# vfd_controller.net
KiCad netlist of a schematic drawn in EAGLE
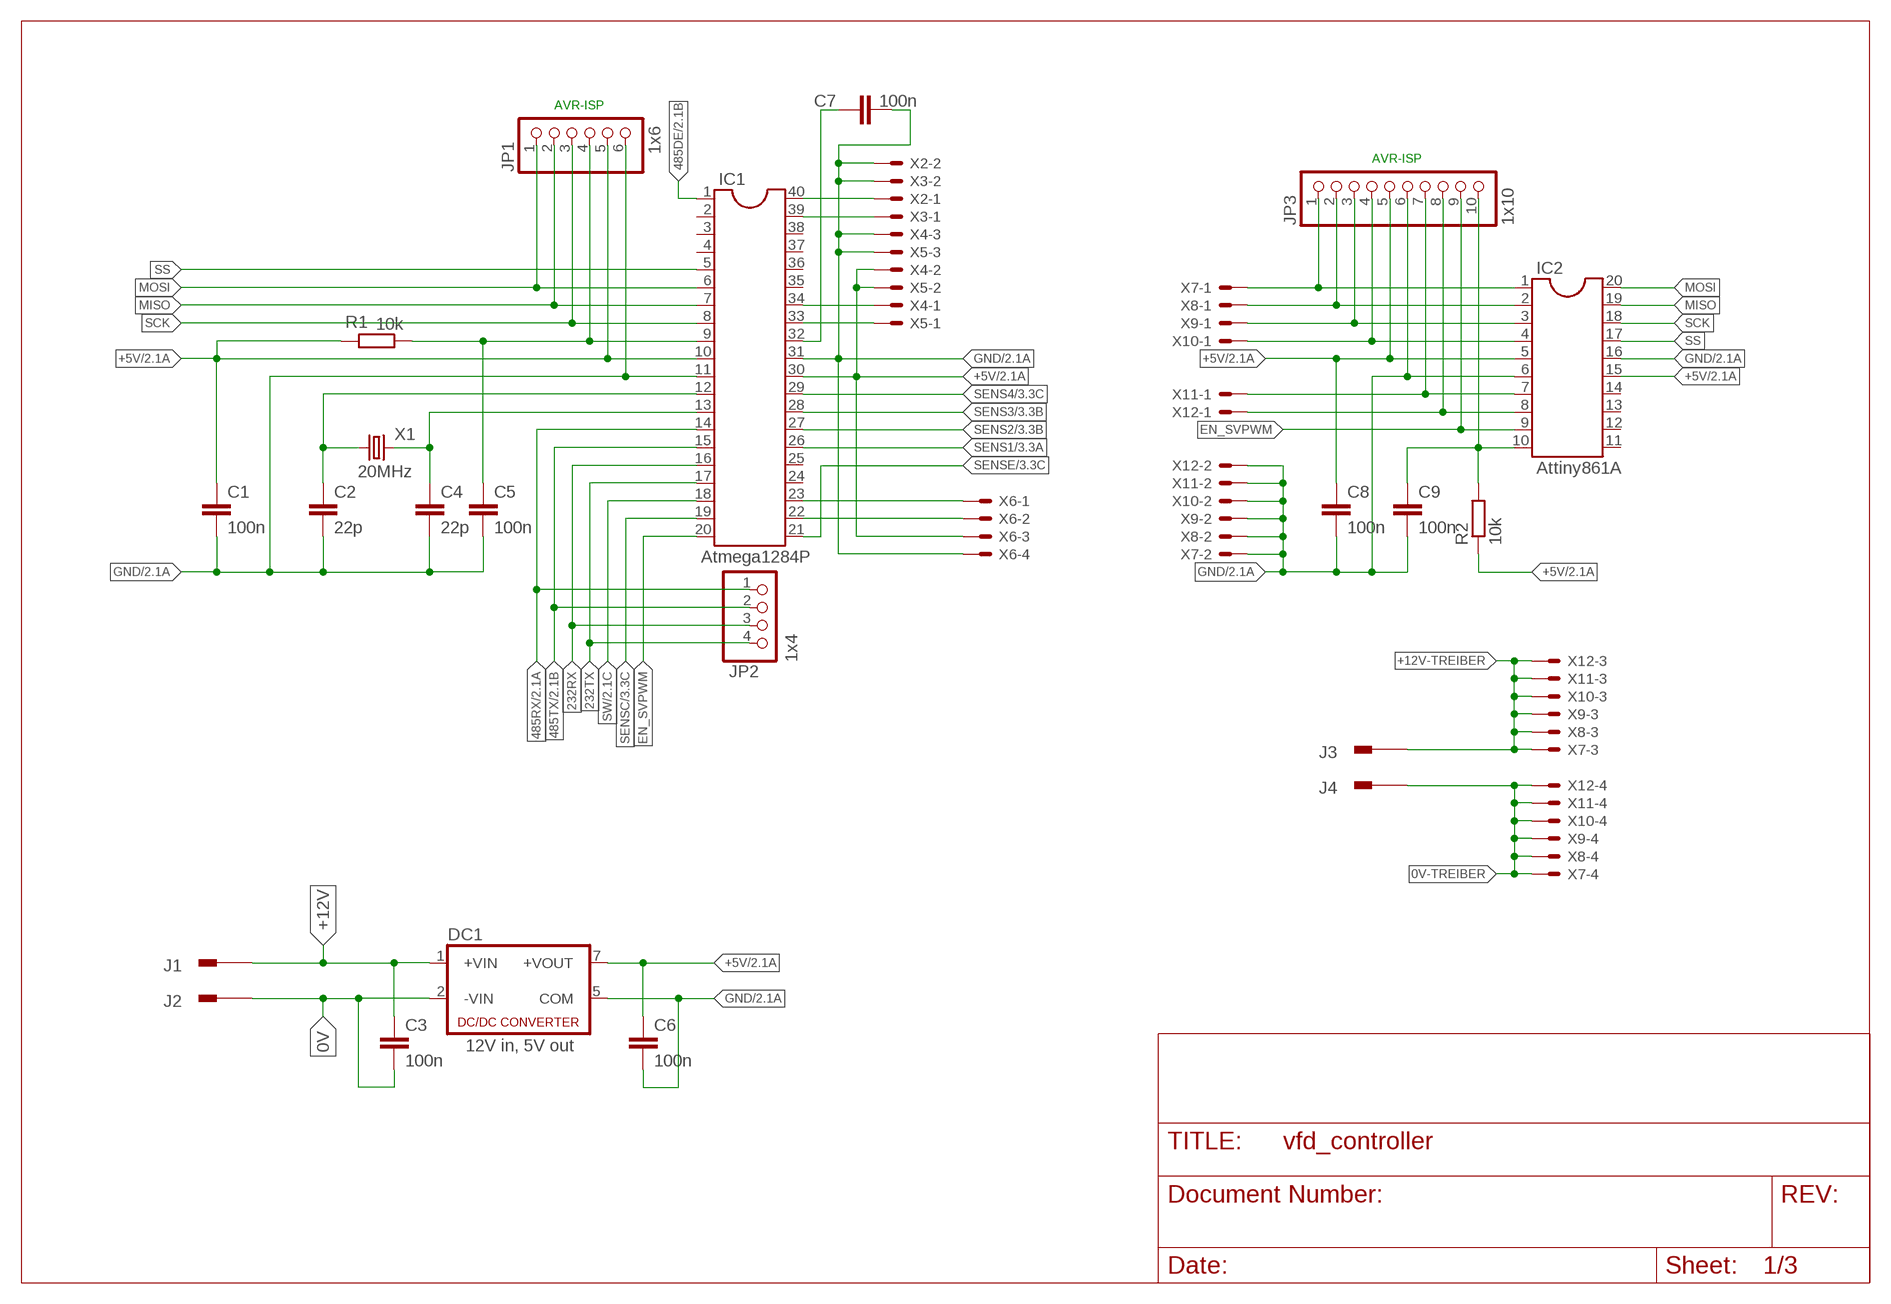
[diagram p0: schematic, sheet 1]
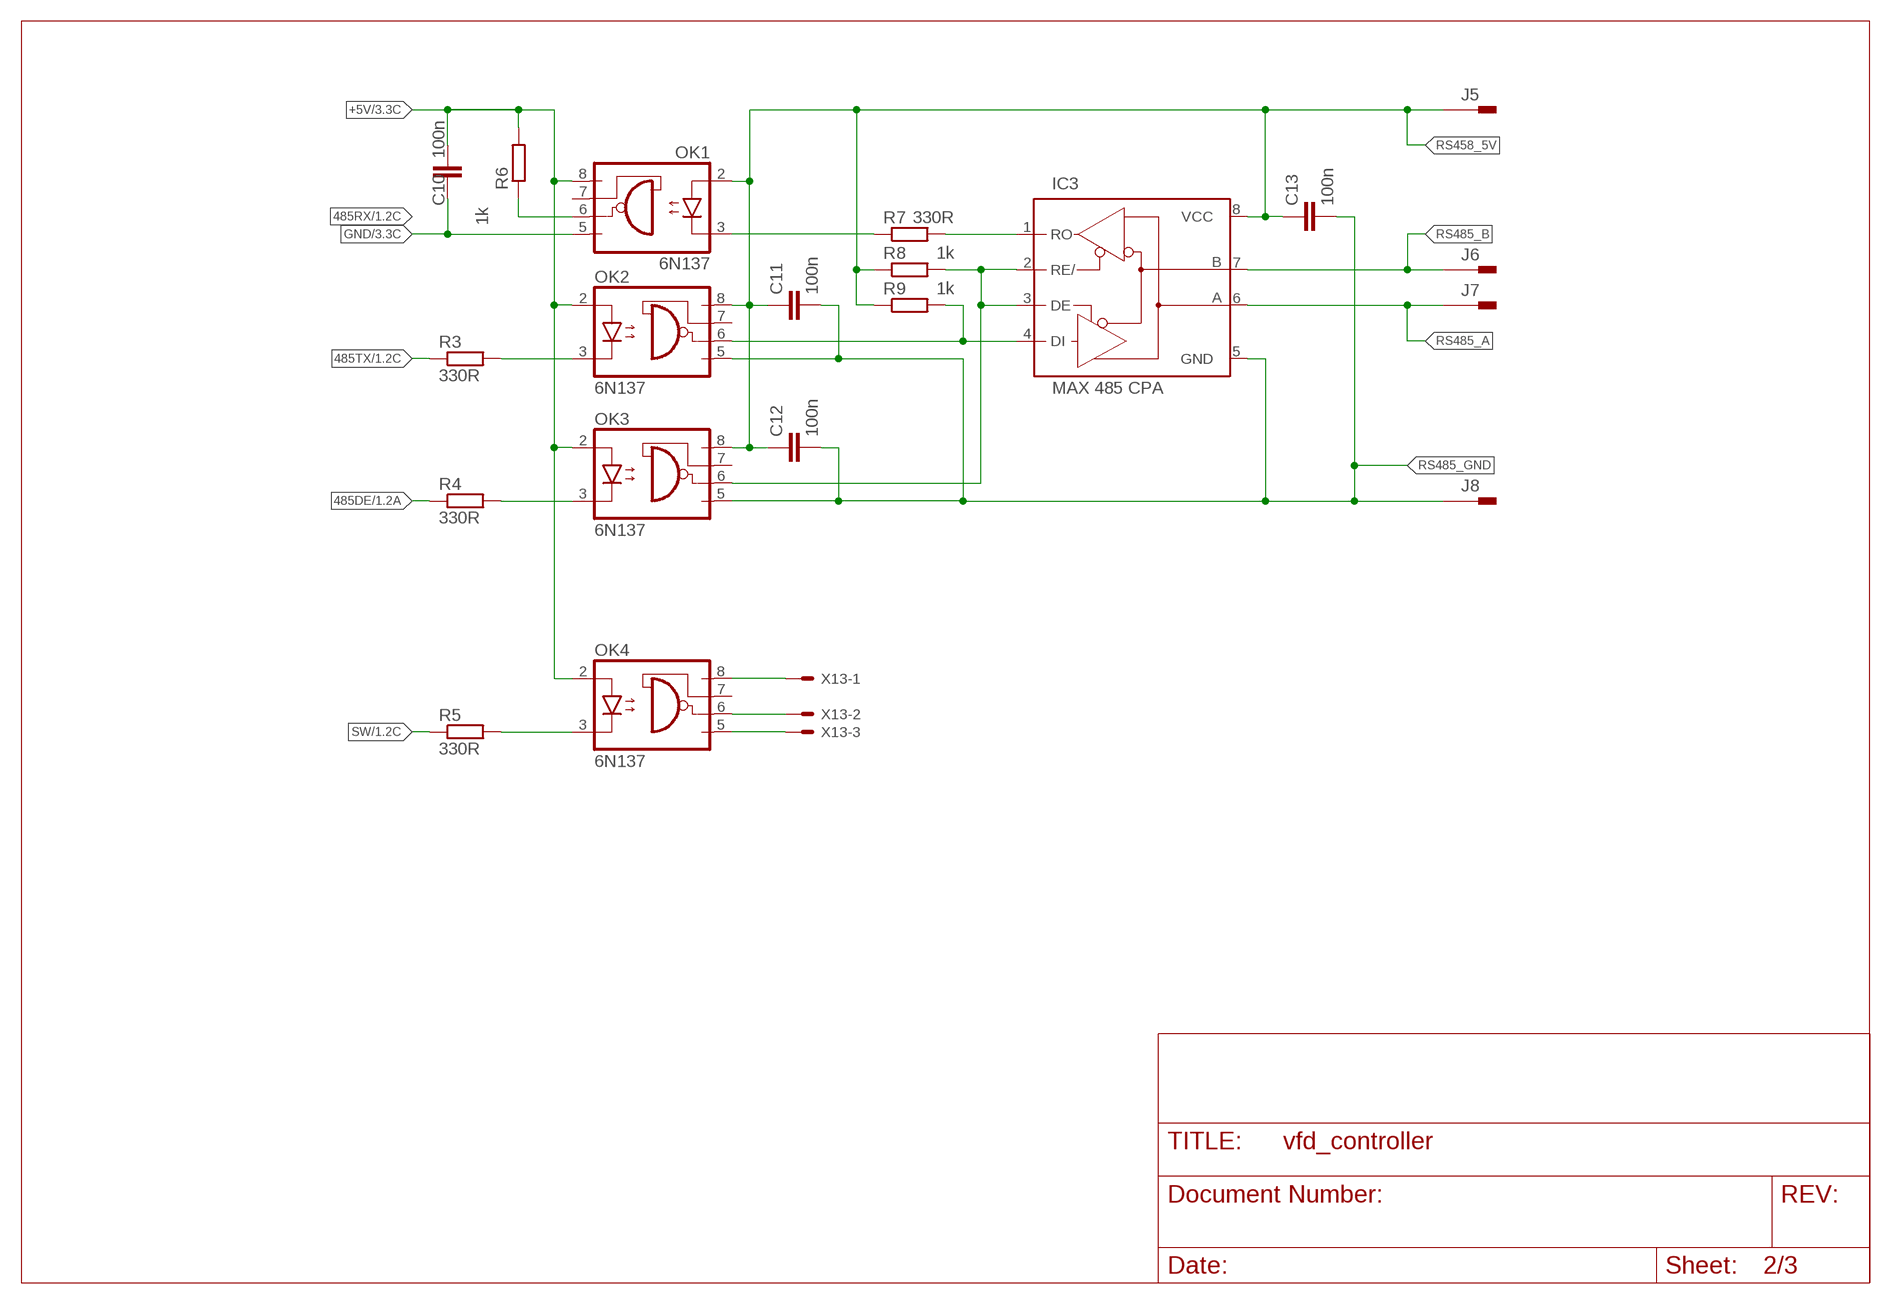
[diagram p1: schematic, sheet 2]
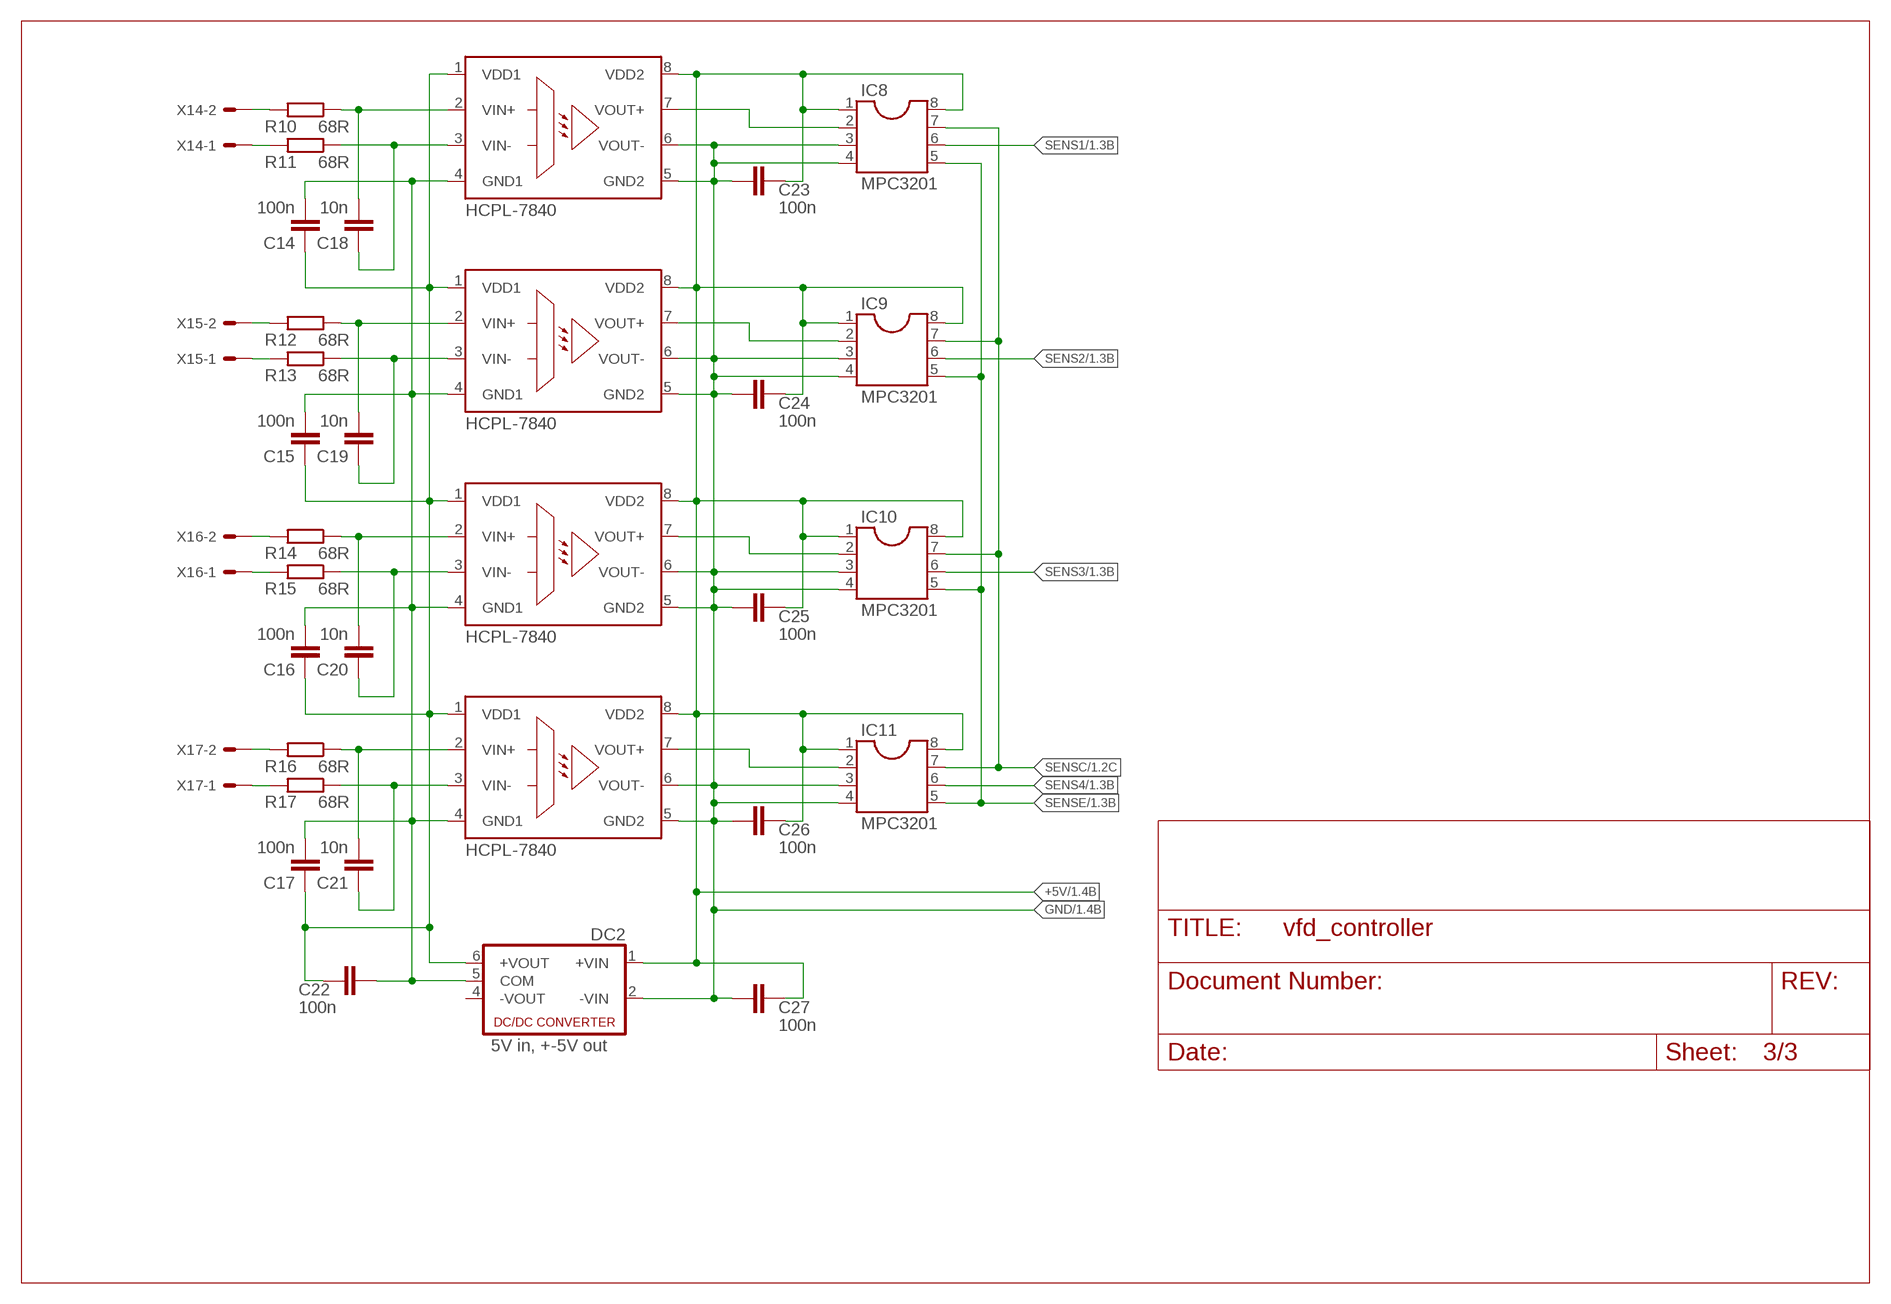
[diagram p2: schematic, sheet 3]

(export (version "E")
  (design (tool "Eeschema 10.0.6"))
  (components
    (comp (ref "C1")
      (value "100n")
      (footprint "eagle-import:C025-024X044")
      (libsource (lib "eagle-import") (part "C-EU025-024X044"))
    )
    (comp (ref "C2")
      (value "22p")
      (footprint "eagle-import:C025-024X044")
      (libsource (lib "eagle-import") (part "C-EU025-024X044"))
    )
    (comp (ref "C3")
      (value "100n")
      (footprint "eagle-import:C025-024X044")
      (libsource (lib "eagle-import") (part "C-EU025-024X044"))
    )
    (comp (ref "C4")
      (value "22p")
      (footprint "eagle-import:C025-024X044")
      (libsource (lib "eagle-import") (part "C-EU025-024X044"))
    )
    (comp (ref "C5")
      (value "100n")
      (footprint "eagle-import:C050-025X075")
      (libsource (lib "eagle-import") (part "C-EU050-025X075"))
    )
    (comp (ref "C6")
      (value "100n")
      (footprint "eagle-import:C050-025X075")
      (libsource (lib "eagle-import") (part "C-EU050-025X075"))
    )
    (comp (ref "C7")
      (value "100n")
      (footprint "eagle-import:C025-024X044")
      (libsource (lib "eagle-import") (part "C-EU025-024X044"))
    )
    (comp (ref "C8")
      (value "100n")
      (footprint "eagle-import:C025-024X044")
      (libsource (lib "eagle-import") (part "C-EU025-024X044"))
    )
    (comp (ref "C9")
      (value "100n")
      (footprint "eagle-import:C025-024X044")
      (libsource (lib "eagle-import") (part "C-EU025-024X044"))
    )
    (comp (ref "DC1")
      (value "12V in, 5V out")
      (footprint "eagle-import:MEV")
      (libsource (lib "eagle-import") (part "MEV"))
    )
    (comp (ref "IC1")
      (value "Atmega1284P")
      (footprint "eagle-import:DIL40")
      (libsource (lib "eagle-import") (part "DIL40"))
    )
    (comp (ref "IC2")
      (value "Attiny861A")
      (footprint "eagle-import:DIL20")
      (libsource (lib "eagle-import") (part "DIL20"))
    )
    (comp (ref "J1")
      (value "PIN2F061.200")
      (footprint "eagle-import:F061.200")
      (libsource (lib "eagle-import") (part "PIN2F061.200"))
    )
    (comp (ref "J2")
      (value "PIN2F061.200")
      (footprint "eagle-import:F061.200")
      (libsource (lib "eagle-import") (part "PIN2F061.200"))
    )
    (comp (ref "J3")
      (value "PIN2F061.200")
      (footprint "eagle-import:F061.200")
      (libsource (lib "eagle-import") (part "PIN2F061.200"))
    )
    (comp (ref "J4")
      (value "PIN2F061.200")
      (footprint "eagle-import:F061.200")
      (libsource (lib "eagle-import") (part "PIN2F061.200"))
    )
    (comp (ref "JP1")
      (value "1x6")
      (footprint "eagle-import:1X06")
      (libsource (lib "eagle-import") (part "PINHD-1X6"))
    )
    (comp (ref "JP2")
      (value "1x4")
      (footprint "eagle-import:1X04")
      (libsource (lib "eagle-import") (part "PINHD-1X4"))
    )
    (comp (ref "JP3")
      (value "1x10")
      (footprint "eagle-import:1X10")
      (libsource (lib "eagle-import") (part "PINHD-1X10"))
    )
    (comp (ref "R1")
      (value "10k")
      (footprint "eagle-import:0204V")
      (libsource (lib "eagle-import") (part "R-EU_0204/2V"))
    )
    (comp (ref "R2")
      (value "10k")
      (footprint "eagle-import:0207_12")
      (libsource (lib "eagle-import") (part "R-EU_0207/12"))
    )
    (comp (ref "X1")
      (value "20MHz")
      (footprint "eagle-import:HC49")
      (libsource (lib "eagle-import") (part "CRYSTALS-NOGND-HC49"))
    )
    (comp (ref "X2")
      (value "JST-XH-02-PIN-LONG-PAD")
      (footprint "eagle-import:JST-XH-02-PACKAGE-LONG-PAD")
      (fields (field (name "R") "JST XH2P ST"))
      (libsource (lib "eagle-import") (part "JST-XH-02-PIN-LONG-PAD"))
    )
    (comp (ref "X3")
      (value "JST-XH-02-PIN-LONG-PAD")
      (footprint "eagle-import:JST-XH-02-PACKAGE-LONG-PAD")
      (fields (field (name "R") "JST XH2P ST"))
      (libsource (lib "eagle-import") (part "JST-XH-02-PIN-LONG-PAD"))
    )
    (comp (ref "X4")
      (value "JST-XH-03-PIN-LONG-PAD")
      (footprint "eagle-import:JST-XH-03-PACKAGE-LONG-PAD")
      (fields (field (name "R") "JST XH3P ST"))
      (libsource (lib "eagle-import") (part "JST-XH-03-PIN-LONG-PAD"))
    )
    (comp (ref "X5")
      (value "JST-XH-03-PIN-LONG-PAD")
      (footprint "eagle-import:JST-XH-03-PACKAGE-LONG-PAD")
      (fields (field (name "R") "JST XH3P ST"))
      (libsource (lib "eagle-import") (part "JST-XH-03-PIN-LONG-PAD"))
    )
    (comp (ref "X6")
      (value "JST-XH-04-PIN-LONG-PAD")
      (footprint "eagle-import:JST-XH-04-PACKAGE-LONG-PAD")
      (fields (field (name "R") "JST XH4P ST"))
      (libsource (lib "eagle-import") (part "JST-XH-04-PIN-LONG-PAD"))
    )
    (comp (ref "X7")
      (value "JST-XH-04-PIN-LONG-PAD")
      (footprint "eagle-import:JST-XH-04-PACKAGE-LONG-PAD")
      (fields (field (name "R") "JST XH4P ST"))
      (libsource (lib "eagle-import") (part "JST-XH-04-PIN-LONG-PAD"))
    )
    (comp (ref "X8")
      (value "JST-XH-04-PIN-LONG-PAD")
      (footprint "eagle-import:JST-XH-04-PACKAGE-LONG-PAD")
      (fields (field (name "R") "JST XH4P ST"))
      (libsource (lib "eagle-import") (part "JST-XH-04-PIN-LONG-PAD"))
    )
    (comp (ref "X9")
      (value "JST-XH-04-PIN-LONG-PAD")
      (footprint "eagle-import:JST-XH-04-PACKAGE-LONG-PAD")
      (fields (field (name "R") "JST XH4P ST"))
      (libsource (lib "eagle-import") (part "JST-XH-04-PIN-LONG-PAD"))
    )
    (comp (ref "X10")
      (value "JST-XH-04-PIN-LONG-PAD")
      (footprint "eagle-import:JST-XH-04-PACKAGE-LONG-PAD")
      (fields (field (name "R") "JST XH4P ST"))
      (libsource (lib "eagle-import") (part "JST-XH-04-PIN-LONG-PAD"))
    )
    (comp (ref "X11")
      (value "JST-XH-04-PIN-LONG-PAD")
      (footprint "eagle-import:JST-XH-04-PACKAGE-LONG-PAD")
      (fields (field (name "R") "JST XH4P ST"))
      (libsource (lib "eagle-import") (part "JST-XH-04-PIN-LONG-PAD"))
    )
    (comp (ref "X12")
      (value "JST-XH-04-PIN-LONG-PAD")
      (footprint "eagle-import:JST-XH-04-PACKAGE-LONG-PAD")
      (fields (field (name "R") "JST XH4P ST"))
      (libsource (lib "eagle-import") (part "JST-XH-04-PIN-LONG-PAD"))
    )
    (comp (ref "C14")
      (value "100n")
      (footprint "eagle-import:C025-024X044")
      (libsource (lib "eagle-import") (part "C-EU025-024X044"))
    )
    (comp (ref "C15")
      (value "100n")
      (footprint "eagle-import:C050-025X075")
      (libsource (lib "eagle-import") (part "C-EU050-025X075"))
    )
    (comp (ref "C16")
      (value "100n")
      (footprint "eagle-import:C050-025X075")
      (libsource (lib "eagle-import") (part "C-EU050-025X075"))
    )
    (comp (ref "C17")
      (value "100n")
      (footprint "eagle-import:C050-025X075")
      (libsource (lib "eagle-import") (part "C-EU050-025X075"))
    )
    (comp (ref "C18")
      (value "10n")
      (footprint "eagle-import:C025-024X044")
      (libsource (lib "eagle-import") (part "C-EU025-024X044"))
    )
    (comp (ref "C19")
      (value "10n")
      (footprint "eagle-import:C025-024X044")
      (libsource (lib "eagle-import") (part "C-EU025-024X044"))
    )
    (comp (ref "C20")
      (value "10n")
      (footprint "eagle-import:C025-024X044")
      (libsource (lib "eagle-import") (part "C-EU025-024X044"))
    )
    (comp (ref "C21")
      (value "10n")
      (footprint "eagle-import:C025-024X044")
      (libsource (lib "eagle-import") (part "C-EU025-024X044"))
    )
    (comp (ref "C22")
      (value "100n")
      (footprint "eagle-import:C025-024X044")
      (libsource (lib "eagle-import") (part "C-EU025-024X044"))
    )
    (comp (ref "C23")
      (value "100n")
      (footprint "eagle-import:C025-024X044")
      (libsource (lib "eagle-import") (part "C-EU025-024X044"))
    )
    (comp (ref "C24")
      (value "100n")
      (footprint "eagle-import:C050-025X075")
      (libsource (lib "eagle-import") (part "C-EU050-025X075"))
    )
    (comp (ref "C25")
      (value "100n")
      (footprint "eagle-import:C050-025X075")
      (libsource (lib "eagle-import") (part "C-EU050-025X075"))
    )
    (comp (ref "C26")
      (value "100n")
      (footprint "eagle-import:C050-025X075")
      (libsource (lib "eagle-import") (part "C-EU050-025X075"))
    )
    (comp (ref "C27")
      (value "100n")
      (footprint "eagle-import:C025-024X044")
      (libsource (lib "eagle-import") (part "C-EU025-024X044"))
    )
    (comp (ref "DC2")
      (value "5V in, +-5V out")
      (footprint "eagle-import:NMA")
      (fields (field (name "MF") "C & D TECHNOLOGIES, INC") (field (name "MPN") "NMA0515SC"))
      (libsource (lib "eagle-import") (part "NMA"))
    )
    (comp (ref "IC4")
      (value "HCPL-7840")
      (footprint "eagle-import:DIL08")
      (fields (field (name "MPN") "HCPL-7800A#500"))
      (libsource (lib "eagle-import") (part "HCPL-7800"))
    )
    (comp (ref "IC5")
      (value "HCPL-7840")
      (footprint "eagle-import:DIL08")
      (fields (field (name "MPN") "HCPL-7800A#500"))
      (libsource (lib "eagle-import") (part "HCPL-7800"))
    )
    (comp (ref "IC6")
      (value "HCPL-7840")
      (footprint "eagle-import:DIL08")
      (fields (field (name "MPN") "HCPL-7800A#500"))
      (libsource (lib "eagle-import") (part "HCPL-7800"))
    )
    (comp (ref "IC7")
      (value "HCPL-7840")
      (footprint "eagle-import:DIL08")
      (fields (field (name "MPN") "HCPL-7800A#500"))
      (libsource (lib "eagle-import") (part "HCPL-7800"))
    )
    (comp (ref "IC8")
      (value "MPC3201")
      (footprint "eagle-import:DIL08")
      (libsource (lib "eagle-import") (part "DIL8"))
    )
    (comp (ref "IC9")
      (value "MPC3201")
      (footprint "eagle-import:DIL08")
      (libsource (lib "eagle-import") (part "DIL8"))
    )
    (comp (ref "IC10")
      (value "MPC3201")
      (footprint "eagle-import:DIL08")
      (libsource (lib "eagle-import") (part "DIL8"))
    )
    (comp (ref "IC11")
      (value "MPC3201")
      (footprint "eagle-import:DIL08")
      (libsource (lib "eagle-import") (part "DIL8"))
    )
    (comp (ref "R10")
      (value "68R")
      (footprint "eagle-import:0204_5")
      (libsource (lib "eagle-import") (part "resistor_348_R-EU_0204/5"))
    )
    (comp (ref "R11")
      (value "68R")
      (footprint "eagle-import:0204_5")
      (libsource (lib "eagle-import") (part "resistor_348_R-EU_0204/5"))
    )
    (comp (ref "R12")
      (value "68R")
      (footprint "eagle-import:0204_5")
      (libsource (lib "eagle-import") (part "resistor_348_R-EU_0204/5"))
    )
    (comp (ref "R13")
      (value "68R")
      (footprint "eagle-import:0204_5")
      (libsource (lib "eagle-import") (part "resistor_348_R-EU_0204/5"))
    )
    (comp (ref "R14")
      (value "68R")
      (footprint "eagle-import:0204_5")
      (libsource (lib "eagle-import") (part "resistor_348_R-EU_0204/5"))
    )
    (comp (ref "R15")
      (value "68R")
      (footprint "eagle-import:0204_5")
      (libsource (lib "eagle-import") (part "resistor_348_R-EU_0204/5"))
    )
    (comp (ref "R16")
      (value "68R")
      (footprint "eagle-import:0204_5")
      (libsource (lib "eagle-import") (part "resistor_348_R-EU_0204/5"))
    )
    (comp (ref "R17")
      (value "68R")
      (footprint "eagle-import:0204_5")
      (libsource (lib "eagle-import") (part "resistor_348_R-EU_0204/5"))
    )
    (comp (ref "X14")
      (value "JST-XH-02-PIN-LONG-PAD")
      (footprint "eagle-import:JST-XH-02-PACKAGE-LONG-PAD")
      (fields (field (name "R") "JST XH2P ST"))
      (libsource (lib "eagle-import") (part "JST-XH-02-PIN-LONG-PAD"))
    )
    (comp (ref "X15")
      (value "JST-XH-02-PIN-LONG-PAD")
      (footprint "eagle-import:JST-XH-02-PACKAGE-LONG-PAD")
      (fields (field (name "R") "JST XH2P ST"))
      (libsource (lib "eagle-import") (part "JST-XH-02-PIN-LONG-PAD"))
    )
    (comp (ref "X16")
      (value "JST-XH-02-PIN-LONG-PAD")
      (footprint "eagle-import:JST-XH-02-PACKAGE-LONG-PAD")
      (fields (field (name "R") "JST XH2P ST"))
      (libsource (lib "eagle-import") (part "JST-XH-02-PIN-LONG-PAD"))
    )
    (comp (ref "X17")
      (value "JST-XH-02-PIN-LONG-PAD")
      (footprint "eagle-import:JST-XH-02-PACKAGE-LONG-PAD")
      (fields (field (name "R") "JST XH2P ST"))
      (libsource (lib "eagle-import") (part "JST-XH-02-PIN-LONG-PAD"))
    )
    (comp (ref "C10")
      (value "100n")
      (footprint "eagle-import:C025-024X044")
      (libsource (lib "eagle-import") (part "resistor_348_C-EU025-024X044"))
    )
    (comp (ref "C11")
      (value "100n")
      (footprint "eagle-import:C025-024X044")
      (libsource (lib "eagle-import") (part "resistor_348_C-EU025-024X044"))
    )
    (comp (ref "C12")
      (value "100n")
      (footprint "eagle-import:C025-024X044")
      (libsource (lib "eagle-import") (part "resistor_348_C-EU025-024X044"))
    )
    (comp (ref "C13")
      (value "100n")
      (footprint "eagle-import:C025-024X044")
      (libsource (lib "eagle-import") (part "resistor_348_C-EU025-024X044"))
    )
    (comp (ref "IC3")
      (value "MAX 485 CPA")
      (footprint "eagle-import:DIL08")
      (libsource (lib "eagle-import") (part "MAX34PA68C"))
    )
    (comp (ref "J5")
      (value "PIN2F061.200")
      (footprint "eagle-import:F061.200")
      (libsource (lib "eagle-import") (part "PIN2F061.200"))
    )
    (comp (ref "J6")
      (value "PIN2F061.200")
      (footprint "eagle-import:F061.200")
      (libsource (lib "eagle-import") (part "PIN2F061.200"))
    )
    (comp (ref "J7")
      (value "PIN2F061.200")
      (footprint "eagle-import:F061.200")
      (libsource (lib "eagle-import") (part "PIN2F061.200"))
    )
    (comp (ref "J8")
      (value "PIN2F061.200")
      (footprint "eagle-import:F061.200")
      (libsource (lib "eagle-import") (part "PIN2F061.200"))
    )
    (comp (ref "OK1")
      (value "6N137")
      (footprint "eagle-import:DIL08")
      (libsource (lib "eagle-import") (part "6N137"))
    )
    (comp (ref "OK2")
      (value "6N137")
      (footprint "eagle-import:DIL08")
      (libsource (lib "eagle-import") (part "6N137"))
    )
    (comp (ref "OK3")
      (value "6N137")
      (footprint "eagle-import:DIL08")
      (libsource (lib "eagle-import") (part "6N137"))
    )
    (comp (ref "OK4")
      (value "6N137")
      (footprint "eagle-import:DIL08")
      (libsource (lib "eagle-import") (part "6N137"))
    )
    (comp (ref "R3")
      (value "330R")
      (footprint "eagle-import:0204_7")
      (libsource (lib "eagle-import") (part "resistor_348_R-EU_0204/7"))
    )
    (comp (ref "R4")
      (value "330R")
      (footprint "eagle-import:0204_7")
      (libsource (lib "eagle-import") (part "resistor_348_R-EU_0204/7"))
    )
    (comp (ref "R5")
      (value "330R")
      (footprint "eagle-import:0207_12")
      (libsource (lib "eagle-import") (part "resistor_348_R-EU_0207/12"))
    )
    (comp (ref "R6")
      (value "1k")
      (footprint "eagle-import:0204_5")
      (libsource (lib "eagle-import") (part "resistor_348_R-EU_0204/5"))
    )
    (comp (ref "R7")
      (value "330R")
      (footprint "eagle-import:0204_5")
      (libsource (lib "eagle-import") (part "resistor_348_R-EU_0204/5"))
    )
    (comp (ref "R8")
      (value "1k")
      (footprint "eagle-import:0204_5")
      (libsource (lib "eagle-import") (part "resistor_348_R-EU_0204/5"))
    )
    (comp (ref "R9")
      (value "1k")
      (footprint "eagle-import:0204_5")
      (libsource (lib "eagle-import") (part "resistor_348_R-EU_0204/5"))
    )
    (comp (ref "X13")
      (value "JST-XH-03-PIN-LONG-PAD")
      (footprint "eagle-import:JST-XH-03-PACKAGE-LONG-PAD")
      (fields (field (name "R") "JST XH3P ST"))
      (libsource (lib "eagle-import") (part "JST-XH-03-PIN-LONG-PAD"))
    )
  )
  (nets
    (net (code "1") (name "+5V") (class "Default")
      (node (ref "C1") (pin "1") (pinfunction "1_1") (pintype "passive"))
      (node (ref "C10") (pin "2") (pinfunction "2_2") (pintype "passive"))
      (node (ref "C23") (pin "2") (pinfunction "2_2") (pintype "passive"))
      (node (ref "C24") (pin "2") (pinfunction "2_2") (pintype "passive"))
      (node (ref "C25") (pin "2") (pinfunction "2_2") (pintype "passive"))
      (node (ref "C26") (pin "2") (pinfunction "2_2") (pintype "passive"))
      (node (ref "C27") (pin "2") (pinfunction "2_2") (pintype "passive"))
      (node (ref "C6") (pin "1") (pinfunction "1_1") (pintype "passive"))
      (node (ref "C8") (pin "1") (pinfunction "1_1") (pintype "passive"))
      (node (ref "DC1") (pin "7") (pinfunction "+VOUT_7") (pintype "passive"))
      (node (ref "DC2") (pin "1") (pinfunction "+VIN_1") (pintype "passive"))
      (node (ref "IC1") (pin "10") (pinfunction "10_10") (pintype "passive"))
      (node (ref "IC1") (pin "30") (pinfunction "30_30") (pintype "passive"))
      (node (ref "IC10") (pin "1") (pinfunction "1_1") (pintype "passive"))
      (node (ref "IC10") (pin "8") (pinfunction "8_8") (pintype "passive"))
      (node (ref "IC11") (pin "1") (pinfunction "1_1") (pintype "passive"))
      (node (ref "IC11") (pin "8") (pinfunction "8_8") (pintype "passive"))
      (node (ref "IC2") (pin "15") (pinfunction "15_15") (pintype "passive"))
      (node (ref "IC2") (pin "5") (pinfunction "5_5") (pintype "passive"))
      (node (ref "IC4") (pin "8") (pinfunction "VDD2_8") (pintype "power_in"))
      (node (ref "IC5") (pin "8") (pinfunction "VDD2_8") (pintype "power_in"))
      (node (ref "IC6") (pin "8") (pinfunction "VDD2_8") (pintype "power_in"))
      (node (ref "IC7") (pin "8") (pinfunction "VDD2_8") (pintype "power_in"))
      (node (ref "IC8") (pin "1") (pinfunction "1_1") (pintype "passive"))
      (node (ref "IC8") (pin "8") (pinfunction "8_8") (pintype "passive"))
      (node (ref "IC9") (pin "1") (pinfunction "1_1") (pintype "passive"))
      (node (ref "IC9") (pin "8") (pinfunction "8_8") (pintype "passive"))
      (node (ref "JP1") (pin "5") (pinfunction "5_5") (pintype "passive"))
      (node (ref "JP3") (pin "5") (pinfunction "5_5") (pintype "passive"))
      (node (ref "OK1") (pin "8") (pinfunction "VCC_8") (pintype "passive"))
      (node (ref "OK2") (pin "2") (pinfunction "A_2") (pintype "passive"))
      (node (ref "OK3") (pin "2") (pinfunction "A_2") (pintype "passive"))
      (node (ref "OK4") (pin "2") (pinfunction "A_2") (pintype "passive"))
      (node (ref "R1") (pin "2") (pinfunction "2_2") (pintype "passive"))
      (node (ref "R2") (pin "1") (pinfunction "1_1") (pintype "passive"))
      (node (ref "R6") (pin "2") (pinfunction "2_2") (pintype "passive"))
      (node (ref "X4") (pin "2") (pinfunction "S_2") (pintype "passive"))
      (node (ref "X5") (pin "2") (pinfunction "S_2") (pintype "passive"))
      (node (ref "X6") (pin "3") (pinfunction "S_3") (pintype "passive"))
    )
    (net (code "2") (name "+12V") (class "Default")
      (node (ref "C3") (pin "1") (pinfunction "1_1") (pintype "passive"))
      (node (ref "DC1") (pin "1") (pinfunction "+VIN_1") (pintype "passive"))
      (node (ref "J1") (pin "1A") (pinfunction "1_1A") (pintype "passive"))
      (node (ref "J1") (pin "1B") (pinfunction "1_1B") (pintype "passive"))
    )
    (net (code "3") (name "+12V-TREIBER") (class "Default")
      (node (ref "J3") (pin "1A") (pinfunction "1_1A") (pintype "passive"))
      (node (ref "J3") (pin "1B") (pinfunction "1_1B") (pintype "passive"))
      (node (ref "X10") (pin "3") (pinfunction "S_3") (pintype "passive"))
      (node (ref "X11") (pin "3") (pinfunction "S_3") (pintype "passive"))
      (node (ref "X12") (pin "3") (pinfunction "S_3") (pintype "passive"))
      (node (ref "X7") (pin "3") (pinfunction "S_3") (pintype "passive"))
      (node (ref "X8") (pin "3") (pinfunction "S_3") (pintype "passive"))
      (node (ref "X9") (pin "3") (pinfunction "S_3") (pintype "passive"))
    )
    (net (code "4") (name "0V") (class "Default")
      (node (ref "C3") (pin "2") (pinfunction "2_2") (pintype "passive"))
      (node (ref "DC1") (pin "2") (pinfunction "-VIN_2") (pintype "passive"))
      (node (ref "J2") (pin "1A") (pinfunction "1_1A") (pintype "passive"))
      (node (ref "J2") (pin "1B") (pinfunction "1_1B") (pintype "passive"))
    )
    (net (code "5") (name "0V-TREIBER") (class "Default")
      (node (ref "J4") (pin "1A") (pinfunction "1_1A") (pintype "passive"))
      (node (ref "J4") (pin "1B") (pinfunction "1_1B") (pintype "passive"))
      (node (ref "X10") (pin "4") (pinfunction "S_4") (pintype "passive"))
      (node (ref "X11") (pin "4") (pinfunction "S_4") (pintype "passive"))
      (node (ref "X12") (pin "4") (pinfunction "S_4") (pintype "passive"))
      (node (ref "X7") (pin "4") (pinfunction "S_4") (pintype "passive"))
      (node (ref "X8") (pin "4") (pinfunction "S_4") (pintype "passive"))
      (node (ref "X9") (pin "4") (pinfunction "S_4") (pintype "passive"))
    )
    (net (code "6") (name "232RX") (class "Default")
      (node (ref "IC1") (pin "16") (pinfunction "16_16") (pintype "passive"))
      (node (ref "JP2") (pin "3") (pinfunction "3_3") (pintype "passive"))
    )
    (net (code "7") (name "232TX") (class "Default")
      (node (ref "IC1") (pin "17") (pinfunction "17_17") (pintype "passive"))
      (node (ref "JP2") (pin "4") (pinfunction "4_4") (pintype "passive"))
    )
    (net (code "8") (name "485DE") (class "Default")
      (node (ref "IC1") (pin "1") (pinfunction "1_1") (pintype "passive"))
      (node (ref "R4") (pin "1") (pinfunction "1_1") (pintype "passive"))
    )
    (net (code "9") (name "485RX") (class "Default")
      (node (ref "IC1") (pin "14") (pinfunction "14_14") (pintype "passive"))
      (node (ref "JP2") (pin "1") (pinfunction "1_1") (pintype "passive"))
      (node (ref "OK1") (pin "6") (pinfunction "VO_6") (pintype "passive"))
      (node (ref "R6") (pin "1") (pinfunction "1_1") (pintype "passive"))
    )
    (net (code "10") (name "485TX") (class "Default")
      (node (ref "IC1") (pin "15") (pinfunction "15_15") (pintype "passive"))
      (node (ref "JP2") (pin "2") (pinfunction "2_2") (pintype "passive"))
      (node (ref "R3") (pin "1") (pinfunction "1_1") (pintype "passive"))
    )
    (net (code "11") (name "EN_SVPWM") (class "Default")
      (node (ref "IC1") (pin "20") (pinfunction "20_20") (pintype "passive"))
      (node (ref "IC2") (pin "9") (pinfunction "9_9") (pintype "passive"))
      (node (ref "JP3") (pin "9") (pinfunction "9_9") (pintype "passive"))
    )
    (net (code "12") (name "GND") (class "Default")
      (node (ref "C1") (pin "2") (pinfunction "2_2") (pintype "passive"))
      (node (ref "C10") (pin "1") (pinfunction "1_1") (pintype "passive"))
      (node (ref "C2") (pin "2") (pinfunction "2_2") (pintype "passive"))
      (node (ref "C23") (pin "1") (pinfunction "1_1") (pintype "passive"))
      (node (ref "C24") (pin "1") (pinfunction "1_1") (pintype "passive"))
      (node (ref "C25") (pin "1") (pinfunction "1_1") (pintype "passive"))
      (node (ref "C26") (pin "1") (pinfunction "1_1") (pintype "passive"))
      (node (ref "C27") (pin "1") (pinfunction "1_1") (pintype "passive"))
      (node (ref "C4") (pin "2") (pinfunction "2_2") (pintype "passive"))
      (node (ref "C5") (pin "2") (pinfunction "2_2") (pintype "passive"))
      (node (ref "C6") (pin "2") (pinfunction "2_2") (pintype "passive"))
      (node (ref "C7") (pin "2") (pinfunction "2_2") (pintype "passive"))
      (node (ref "C8") (pin "2") (pinfunction "2_2") (pintype "passive"))
      (node (ref "C9") (pin "2") (pinfunction "2_2") (pintype "passive"))
      (node (ref "DC1") (pin "5") (pinfunction "COM_5") (pintype "passive"))
      (node (ref "DC2") (pin "2") (pinfunction "-VIN_2") (pintype "passive"))
      (node (ref "IC1") (pin "11") (pinfunction "11_11") (pintype "passive"))
      (node (ref "IC1") (pin "31") (pinfunction "31_31") (pintype "passive"))
      (node (ref "IC10") (pin "3") (pinfunction "3_3") (pintype "passive"))
      (node (ref "IC10") (pin "4") (pinfunction "4_4") (pintype "passive"))
      (node (ref "IC11") (pin "3") (pinfunction "3_3") (pintype "passive"))
      (node (ref "IC11") (pin "4") (pinfunction "4_4") (pintype "passive"))
      (node (ref "IC2") (pin "16") (pinfunction "16_16") (pintype "passive"))
      (node (ref "IC2") (pin "6") (pinfunction "6_6") (pintype "passive"))
      (node (ref "IC4") (pin "5") (pinfunction "GND2_5") (pintype "power_in"))
      (node (ref "IC4") (pin "6") (pinfunction "VOUT-_6") (pintype "power_in"))
      (node (ref "IC5") (pin "5") (pinfunction "GND2_5") (pintype "power_in"))
      (node (ref "IC5") (pin "6") (pinfunction "VOUT-_6") (pintype "power_in"))
      (node (ref "IC6") (pin "5") (pinfunction "GND2_5") (pintype "power_in"))
      (node (ref "IC6") (pin "6") (pinfunction "VOUT-_6") (pintype "power_in"))
      (node (ref "IC7") (pin "5") (pinfunction "GND2_5") (pintype "power_in"))
      (node (ref "IC7") (pin "6") (pinfunction "VOUT-_6") (pintype "power_in"))
      (node (ref "IC8") (pin "3") (pinfunction "3_3") (pintype "passive"))
      (node (ref "IC8") (pin "4") (pinfunction "4_4") (pintype "passive"))
      (node (ref "IC9") (pin "3") (pinfunction "3_3") (pintype "passive"))
      (node (ref "IC9") (pin "4") (pinfunction "4_4") (pintype "passive"))
      (node (ref "JP1") (pin "6") (pinfunction "6_6") (pintype "passive"))
      (node (ref "JP3") (pin "6") (pinfunction "6_6") (pintype "passive"))
      (node (ref "OK1") (pin "5") (pinfunction "GND_5") (pintype "passive"))
      (node (ref "X10") (pin "2") (pinfunction "S_2") (pintype "passive"))
      (node (ref "X11") (pin "2") (pinfunction "S_2") (pintype "passive"))
      (node (ref "X12") (pin "2") (pinfunction "S_2") (pintype "passive"))
      (node (ref "X2") (pin "2") (pinfunction "S_2") (pintype "passive"))
      (node (ref "X3") (pin "2") (pinfunction "S_2") (pintype "passive"))
      (node (ref "X4") (pin "3") (pinfunction "S_3") (pintype "passive"))
      (node (ref "X5") (pin "3") (pinfunction "S_3") (pintype "passive"))
      (node (ref "X6") (pin "4") (pinfunction "S_4") (pintype "passive"))
      (node (ref "X7") (pin "2") (pinfunction "S_2") (pintype "passive"))
      (node (ref "X8") (pin "2") (pinfunction "S_2") (pintype "passive"))
      (node (ref "X9") (pin "2") (pinfunction "S_2") (pintype "passive"))
    )
    (net (code "13") (name "MISO") (class "Default")
      (node (ref "IC1") (pin "7") (pinfunction "7_7") (pintype "passive"))
      (node (ref "IC2") (pin "19") (pinfunction "19_19") (pintype "passive"))
      (node (ref "JP1") (pin "2") (pinfunction "2_2") (pintype "passive"))
    )
    (net (code "14") (name "MOSI") (class "Default")
      (node (ref "IC1") (pin "6") (pinfunction "6_6") (pintype "passive"))
      (node (ref "IC2") (pin "20") (pinfunction "20_20") (pintype "passive"))
      (node (ref "JP1") (pin "1") (pinfunction "1_1") (pintype "passive"))
    )
    (net (code "15") (name "Net-(C2-Pad1)") (class "Default")
      (node (ref "C2") (pin "1") (pinfunction "1_1") (pintype "passive"))
      (node (ref "IC1") (pin "12") (pinfunction "12_12") (pintype "passive"))
      (node (ref "X1") (pin "1") (pinfunction "1_1") (pintype "passive"))
    )
    (net (code "16") (name "Net-(C4-Pad1)") (class "Default")
      (node (ref "C4") (pin "1") (pinfunction "1_1") (pintype "passive"))
      (node (ref "IC1") (pin "13") (pinfunction "13_13") (pintype "passive"))
      (node (ref "X1") (pin "2") (pinfunction "2_2") (pintype "passive"))
    )
    (net (code "17") (name "Net-(C5-Pad1)") (class "Default")
      (node (ref "C5") (pin "1") (pinfunction "1_1") (pintype "passive"))
      (node (ref "IC1") (pin "9") (pinfunction "9_9") (pintype "passive"))
      (node (ref "JP1") (pin "4") (pinfunction "4_4") (pintype "passive"))
      (node (ref "R1") (pin "1") (pinfunction "1_1") (pintype "passive"))
    )
    (net (code "18") (name "Net-(C7-Pad1)") (class "Default")
      (node (ref "C7") (pin "1") (pinfunction "1_1") (pintype "passive"))
      (node (ref "IC1") (pin "32") (pinfunction "32_32") (pintype "passive"))
    )
    (net (code "19") (name "Net-(C9-Pad1)") (class "Default")
      (node (ref "C9") (pin "1") (pinfunction "1_1") (pintype "passive"))
      (node (ref "IC2") (pin "10") (pinfunction "10_10") (pintype "passive"))
      (node (ref "JP3") (pin "10") (pinfunction "10_10") (pintype "passive"))
      (node (ref "R2") (pin "2") (pinfunction "2_2") (pintype "passive"))
    )
    (net (code "20") (name "Net-(DC2-+VOUT)") (class "Default")
      (node (ref "C14") (pin "1") (pinfunction "1_1") (pintype "passive"))
      (node (ref "C15") (pin "1") (pinfunction "1_1") (pintype "passive"))
      (node (ref "C16") (pin "1") (pinfunction "1_1") (pintype "passive"))
      (node (ref "C17") (pin "1") (pinfunction "1_1") (pintype "passive"))
      (node (ref "C22") (pin "2") (pinfunction "2_2") (pintype "passive"))
      (node (ref "DC2") (pin "6") (pinfunction "+VOUT_6") (pintype "passive"))
      (node (ref "IC4") (pin "1") (pinfunction "VDD1_1") (pintype "power_in"))
      (node (ref "IC5") (pin "1") (pinfunction "VDD1_1") (pintype "power_in"))
      (node (ref "IC6") (pin "1") (pinfunction "VDD1_1") (pintype "power_in"))
      (node (ref "IC7") (pin "1") (pinfunction "VDD1_1") (pintype "power_in"))
    )
    (net (code "21") (name "Net-(DC2-COM)") (class "Default")
      (node (ref "C14") (pin "2") (pinfunction "2_2") (pintype "passive"))
      (node (ref "C15") (pin "2") (pinfunction "2_2") (pintype "passive"))
      (node (ref "C16") (pin "2") (pinfunction "2_2") (pintype "passive"))
      (node (ref "C17") (pin "2") (pinfunction "2_2") (pintype "passive"))
      (node (ref "C22") (pin "1") (pinfunction "1_1") (pintype "passive"))
      (node (ref "DC2") (pin "5") (pinfunction "COM_5") (pintype "passive"))
      (node (ref "IC4") (pin "4") (pinfunction "GND1_4") (pintype "power_in"))
      (node (ref "IC5") (pin "4") (pinfunction "GND1_4") (pintype "power_in"))
      (node (ref "IC6") (pin "4") (pinfunction "GND1_4") (pintype "power_in"))
      (node (ref "IC7") (pin "4") (pinfunction "GND1_4") (pintype "power_in"))
    )
    (net (code "22") (name "Net-(IC3-DE)") (class "Default")
      (node (ref "IC3") (pin "2") (pinfunction "RE/_2") (pintype "input"))
      (node (ref "IC3") (pin "3") (pinfunction "DE_3") (pintype "input"))
      (node (ref "OK3") (pin "6") (pinfunction "VO_6") (pintype "passive"))
      (node (ref "R8") (pin "2") (pinfunction "2_2") (pintype "passive"))
    )
    (net (code "23") (name "Net-(IC3-DI)") (class "Default")
      (node (ref "IC3") (pin "4") (pinfunction "DI_4") (pintype "input"))
      (node (ref "OK2") (pin "6") (pinfunction "VO_6") (pintype "passive"))
      (node (ref "R9") (pin "2") (pinfunction "2_2") (pintype "passive"))
    )
    (net (code "24") (name "Net-(IC3-RO)") (class "Default")
      (node (ref "IC3") (pin "1") (pinfunction "RO_1") (pintype "output"))
      (node (ref "R7") (pin "2") (pinfunction "2_2") (pintype "passive"))
    )
    (net (code "25") (name "Net-(IC4-VIN+)") (class "Default")
      (node (ref "C18") (pin "2") (pinfunction "2_2") (pintype "passive"))
      (node (ref "IC4") (pin "2") (pinfunction "VIN+_2") (pintype "power_in"))
      (node (ref "R10") (pin "1") (pinfunction "1_1") (pintype "passive"))
    )
    (net (code "26") (name "Net-(IC4-VIN-)") (class "Default")
      (node (ref "C18") (pin "1") (pinfunction "1_1") (pintype "passive"))
      (node (ref "IC4") (pin "3") (pinfunction "VIN-_3") (pintype "power_in"))
      (node (ref "R11") (pin "1") (pinfunction "1_1") (pintype "passive"))
    )
    (net (code "27") (name "Net-(IC4-VOUT+)") (class "Default")
      (node (ref "IC4") (pin "7") (pinfunction "VOUT+_7") (pintype "power_in"))
      (node (ref "IC8") (pin "2") (pinfunction "2_2") (pintype "passive"))
    )
    (net (code "28") (name "Net-(IC5-VIN+)") (class "Default")
      (node (ref "C19") (pin "2") (pinfunction "2_2") (pintype "passive"))
      (node (ref "IC5") (pin "2") (pinfunction "VIN+_2") (pintype "power_in"))
      (node (ref "R12") (pin "1") (pinfunction "1_1") (pintype "passive"))
    )
    (net (code "29") (name "Net-(IC5-VIN-)") (class "Default")
      (node (ref "C19") (pin "1") (pinfunction "1_1") (pintype "passive"))
      (node (ref "IC5") (pin "3") (pinfunction "VIN-_3") (pintype "power_in"))
      (node (ref "R13") (pin "1") (pinfunction "1_1") (pintype "passive"))
    )
    (net (code "30") (name "Net-(IC5-VOUT+)") (class "Default")
      (node (ref "IC5") (pin "7") (pinfunction "VOUT+_7") (pintype "power_in"))
      (node (ref "IC9") (pin "2") (pinfunction "2_2") (pintype "passive"))
    )
    (net (code "31") (name "Net-(IC6-VIN+)") (class "Default")
      (node (ref "C20") (pin "2") (pinfunction "2_2") (pintype "passive"))
      (node (ref "IC6") (pin "2") (pinfunction "VIN+_2") (pintype "power_in"))
      (node (ref "R14") (pin "1") (pinfunction "1_1") (pintype "passive"))
    )
    (net (code "32") (name "Net-(IC6-VIN-)") (class "Default")
      (node (ref "C20") (pin "1") (pinfunction "1_1") (pintype "passive"))
      (node (ref "IC6") (pin "3") (pinfunction "VIN-_3") (pintype "power_in"))
      (node (ref "R15") (pin "1") (pinfunction "1_1") (pintype "passive"))
    )
    (net (code "33") (name "Net-(IC6-VOUT+)") (class "Default")
      (node (ref "IC10") (pin "2") (pinfunction "2_2") (pintype "passive"))
      (node (ref "IC6") (pin "7") (pinfunction "VOUT+_7") (pintype "power_in"))
    )
    (net (code "34") (name "Net-(IC7-VIN+)") (class "Default")
      (node (ref "C21") (pin "2") (pinfunction "2_2") (pintype "passive"))
      (node (ref "IC7") (pin "2") (pinfunction "VIN+_2") (pintype "power_in"))
      (node (ref "R16") (pin "1") (pinfunction "1_1") (pintype "passive"))
    )
    (net (code "35") (name "Net-(IC7-VIN-)") (class "Default")
      (node (ref "C21") (pin "1") (pinfunction "1_1") (pintype "passive"))
      (node (ref "IC7") (pin "3") (pinfunction "VIN-_3") (pintype "power_in"))
      (node (ref "R17") (pin "1") (pinfunction "1_1") (pintype "passive"))
    )
    (net (code "36") (name "Net-(IC7-VOUT+)") (class "Default")
      (node (ref "IC11") (pin "2") (pinfunction "2_2") (pintype "passive"))
      (node (ref "IC7") (pin "7") (pinfunction "VOUT+_7") (pintype "power_in"))
    )
    (net (code "37") (name "Net-(OK1-C)") (class "Default")
      (node (ref "OK1") (pin "3") (pinfunction "C_3") (pintype "passive"))
      (node (ref "R7") (pin "1") (pinfunction "1_1") (pintype "passive"))
    )
    (net (code "38") (name "Net-(OK2-C)") (class "Default")
      (node (ref "OK2") (pin "3") (pinfunction "C_3") (pintype "passive"))
      (node (ref "R3") (pin "2") (pinfunction "2_2") (pintype "passive"))
    )
    (net (code "39") (name "Net-(OK3-C)") (class "Default")
      (node (ref "OK3") (pin "3") (pinfunction "C_3") (pintype "passive"))
      (node (ref "R4") (pin "2") (pinfunction "2_2") (pintype "passive"))
    )
    (net (code "40") (name "Net-(OK4-C)") (class "Default")
      (node (ref "OK4") (pin "3") (pinfunction "C_3") (pintype "passive"))
      (node (ref "R5") (pin "2") (pinfunction "2_2") (pintype "passive"))
    )
    (net (code "41") (name "Net-(OK4-GND)") (class "Default")
      (node (ref "OK4") (pin "5") (pinfunction "GND_5") (pintype "passive"))
      (node (ref "X13") (pin "3") (pinfunction "S_3") (pintype "passive"))
    )
    (net (code "42") (name "Net-(OK4-VCC)") (class "Default")
      (node (ref "OK4") (pin "8") (pinfunction "VCC_8") (pintype "passive"))
      (node (ref "X13") (pin "1") (pinfunction "S_1") (pintype "passive"))
    )
    (net (code "43") (name "Net-(OK4-VO)") (class "Default")
      (node (ref "OK4") (pin "6") (pinfunction "VO_6") (pintype "passive"))
      (node (ref "X13") (pin "2") (pinfunction "S_2") (pintype "passive"))
    )
    (net (code "44") (name "Net-(X2A-S)") (class "Default")
      (node (ref "IC1") (pin "40") (pinfunction "40_40") (pintype "passive"))
      (node (ref "X2") (pin "1") (pinfunction "S_1") (pintype "passive"))
    )
    (net (code "45") (name "Net-(X3A-S)") (class "Default")
      (node (ref "IC1") (pin "39") (pinfunction "39_39") (pintype "passive"))
      (node (ref "X3") (pin "1") (pinfunction "S_1") (pintype "passive"))
    )
    (net (code "46") (name "Net-(X4A-S)") (class "Default")
      (node (ref "IC1") (pin "34") (pinfunction "34_34") (pintype "passive"))
      (node (ref "X4") (pin "1") (pinfunction "S_1") (pintype "passive"))
    )
    (net (code "47") (name "Net-(X5A-S)") (class "Default")
      (node (ref "IC1") (pin "33") (pinfunction "33_33") (pintype "passive"))
      (node (ref "X5") (pin "1") (pinfunction "S_1") (pintype "passive"))
    )
    (net (code "48") (name "Net-(X6A-S)") (class "Default")
      (node (ref "IC1") (pin "23") (pinfunction "23_23") (pintype "passive"))
      (node (ref "X6") (pin "1") (pinfunction "S_1") (pintype "passive"))
    )
    (net (code "49") (name "Net-(X6B-S)") (class "Default")
      (node (ref "IC1") (pin "22") (pinfunction "22_22") (pintype "passive"))
      (node (ref "X6") (pin "2") (pinfunction "S_2") (pintype "passive"))
    )
    (net (code "50") (name "Net-(X7A-S)") (class "Default")
      (node (ref "IC2") (pin "1") (pinfunction "1_1") (pintype "passive"))
      (node (ref "JP3") (pin "1") (pinfunction "1_1") (pintype "passive"))
      (node (ref "X7") (pin "1") (pinfunction "S_1") (pintype "passive"))
    )
    (net (code "51") (name "Net-(X8A-S)") (class "Default")
      (node (ref "IC2") (pin "2") (pinfunction "2_2") (pintype "passive"))
      (node (ref "JP3") (pin "2") (pinfunction "2_2") (pintype "passive"))
      (node (ref "X8") (pin "1") (pinfunction "S_1") (pintype "passive"))
    )
    (net (code "52") (name "Net-(X9A-S)") (class "Default")
      (node (ref "IC2") (pin "3") (pinfunction "3_3") (pintype "passive"))
      (node (ref "JP3") (pin "3") (pinfunction "3_3") (pintype "passive"))
      (node (ref "X9") (pin "1") (pinfunction "S_1") (pintype "passive"))
    )
    (net (code "53") (name "Net-(X10A-S)") (class "Default")
      (node (ref "IC2") (pin "4") (pinfunction "4_4") (pintype "passive"))
      (node (ref "JP3") (pin "4") (pinfunction "4_4") (pintype "passive"))
      (node (ref "X10") (pin "1") (pinfunction "S_1") (pintype "passive"))
    )
    (net (code "54") (name "Net-(X11A-S)") (class "Default")
      (node (ref "IC2") (pin "7") (pinfunction "7_7") (pintype "passive"))
      (node (ref "JP3") (pin "7") (pinfunction "7_7") (pintype "passive"))
      (node (ref "X11") (pin "1") (pinfunction "S_1") (pintype "passive"))
    )
    (net (code "55") (name "Net-(X12A-S)") (class "Default")
      (node (ref "IC2") (pin "8") (pinfunction "8_8") (pintype "passive"))
      (node (ref "JP3") (pin "8") (pinfunction "8_8") (pintype "passive"))
      (node (ref "X12") (pin "1") (pinfunction "S_1") (pintype "passive"))
    )
    (net (code "56") (name "Net-(X14A-S)") (class "Default")
      (node (ref "R11") (pin "2") (pinfunction "2_2") (pintype "passive"))
      (node (ref "X14") (pin "1") (pinfunction "S_1") (pintype "passive"))
    )
    (net (code "57") (name "Net-(X14B-S)") (class "Default")
      (node (ref "R10") (pin "2") (pinfunction "2_2") (pintype "passive"))
      (node (ref "X14") (pin "2") (pinfunction "S_2") (pintype "passive"))
    )
    (net (code "58") (name "Net-(X15A-S)") (class "Default")
      (node (ref "R13") (pin "2") (pinfunction "2_2") (pintype "passive"))
      (node (ref "X15") (pin "1") (pinfunction "S_1") (pintype "passive"))
    )
    (net (code "59") (name "Net-(X15B-S)") (class "Default")
      (node (ref "R12") (pin "2") (pinfunction "2_2") (pintype "passive"))
      (node (ref "X15") (pin "2") (pinfunction "S_2") (pintype "passive"))
    )
    (net (code "60") (name "Net-(X16A-S)") (class "Default")
      (node (ref "R15") (pin "2") (pinfunction "2_2") (pintype "passive"))
      (node (ref "X16") (pin "1") (pinfunction "S_1") (pintype "passive"))
    )
    (net (code "61") (name "Net-(X16B-S)") (class "Default")
      (node (ref "R14") (pin "2") (pinfunction "2_2") (pintype "passive"))
      (node (ref "X16") (pin "2") (pinfunction "S_2") (pintype "passive"))
    )
    (net (code "62") (name "Net-(X17A-S)") (class "Default")
      (node (ref "R17") (pin "2") (pinfunction "2_2") (pintype "passive"))
      (node (ref "X17") (pin "1") (pinfunction "S_1") (pintype "passive"))
    )
    (net (code "63") (name "Net-(X17B-S)") (class "Default")
      (node (ref "R16") (pin "2") (pinfunction "2_2") (pintype "passive"))
      (node (ref "X17") (pin "2") (pinfunction "S_2") (pintype "passive"))
    )
    (net (code "64") (name "RS458_5V") (class "Default")
      (node (ref "C11") (pin "1") (pinfunction "1_1") (pintype "passive"))
      (node (ref "C12") (pin "1") (pinfunction "1_1") (pintype "passive"))
      (node (ref "C13") (pin "1") (pinfunction "1_1") (pintype "passive"))
      (node (ref "IC3") (pin "8") (pinfunction "VCC_8") (pintype "power_in"))
      (node (ref "J5") (pin "1A") (pinfunction "1_1A") (pintype "passive"))
      (node (ref "J5") (pin "1B") (pinfunction "1_1B") (pintype "passive"))
      (node (ref "OK1") (pin "2") (pinfunction "A_2") (pintype "passive"))
      (node (ref "OK2") (pin "8") (pinfunction "VCC_8") (pintype "passive"))
      (node (ref "OK3") (pin "8") (pinfunction "VCC_8") (pintype "passive"))
      (node (ref "R8") (pin "1") (pinfunction "1_1") (pintype "passive"))
      (node (ref "R9") (pin "1") (pinfunction "1_1") (pintype "passive"))
    )
    (net (code "65") (name "RS485_A") (class "Default")
      (node (ref "IC3") (pin "6") (pinfunction "A_6") (pintype "passive"))
      (node (ref "J7") (pin "1A") (pinfunction "1_1A") (pintype "passive"))
      (node (ref "J7") (pin "1B") (pinfunction "1_1B") (pintype "passive"))
    )
    (net (code "66") (name "RS485_B") (class "Default")
      (node (ref "IC3") (pin "7") (pinfunction "B_7") (pintype "passive"))
      (node (ref "J6") (pin "1A") (pinfunction "1_1A") (pintype "passive"))
      (node (ref "J6") (pin "1B") (pinfunction "1_1B") (pintype "passive"))
    )
    (net (code "67") (name "RS485_GND") (class "Default")
      (node (ref "C11") (pin "2") (pinfunction "2_2") (pintype "passive"))
      (node (ref "C12") (pin "2") (pinfunction "2_2") (pintype "passive"))
      (node (ref "C13") (pin "2") (pinfunction "2_2") (pintype "passive"))
      (node (ref "IC3") (pin "5") (pinfunction "GND_5") (pintype "power_in"))
      (node (ref "J8") (pin "1A") (pinfunction "1_1A") (pintype "passive"))
      (node (ref "J8") (pin "1B") (pinfunction "1_1B") (pintype "passive"))
      (node (ref "OK2") (pin "5") (pinfunction "GND_5") (pintype "passive"))
      (node (ref "OK3") (pin "5") (pinfunction "GND_5") (pintype "passive"))
    )
    (net (code "68") (name "SCK") (class "Default")
      (node (ref "IC1") (pin "8") (pinfunction "8_8") (pintype "passive"))
      (node (ref "IC2") (pin "18") (pinfunction "18_18") (pintype "passive"))
      (node (ref "JP1") (pin "3") (pinfunction "3_3") (pintype "passive"))
    )
    (net (code "69") (name "SENS1") (class "Default")
      (node (ref "IC1") (pin "26") (pinfunction "26_26") (pintype "passive"))
      (node (ref "IC8") (pin "6") (pinfunction "6_6") (pintype "passive"))
    )
    (net (code "70") (name "SENS2") (class "Default")
      (node (ref "IC1") (pin "27") (pinfunction "27_27") (pintype "passive"))
      (node (ref "IC9") (pin "6") (pinfunction "6_6") (pintype "passive"))
    )
    (net (code "71") (name "SENS3") (class "Default")
      (node (ref "IC1") (pin "28") (pinfunction "28_28") (pintype "passive"))
      (node (ref "IC10") (pin "6") (pinfunction "6_6") (pintype "passive"))
    )
    (net (code "72") (name "SENS4") (class "Default")
      (node (ref "IC1") (pin "29") (pinfunction "29_29") (pintype "passive"))
      (node (ref "IC11") (pin "6") (pinfunction "6_6") (pintype "passive"))
    )
    (net (code "73") (name "SENSC") (class "Default")
      (node (ref "IC1") (pin "19") (pinfunction "19_19") (pintype "passive"))
      (node (ref "IC10") (pin "7") (pinfunction "7_7") (pintype "passive"))
      (node (ref "IC11") (pin "7") (pinfunction "7_7") (pintype "passive"))
      (node (ref "IC8") (pin "7") (pinfunction "7_7") (pintype "passive"))
      (node (ref "IC9") (pin "7") (pinfunction "7_7") (pintype "passive"))
    )
    (net (code "74") (name "SENSE") (class "Default")
      (node (ref "IC1") (pin "21") (pinfunction "21_21") (pintype "passive"))
      (node (ref "IC10") (pin "5") (pinfunction "5_5") (pintype "passive"))
      (node (ref "IC11") (pin "5") (pinfunction "5_5") (pintype "passive"))
      (node (ref "IC8") (pin "5") (pinfunction "5_5") (pintype "passive"))
      (node (ref "IC9") (pin "5") (pinfunction "5_5") (pintype "passive"))
    )
    (net (code "75") (name "SS") (class "Default")
      (node (ref "IC1") (pin "5") (pinfunction "5_5") (pintype "passive"))
      (node (ref "IC2") (pin "17") (pinfunction "17_17") (pintype "passive"))
    )
    (net (code "76") (name "SW") (class "Default")
      (node (ref "IC1") (pin "18") (pinfunction "18_18") (pintype "passive"))
      (node (ref "R5") (pin "1") (pinfunction "1_1") (pintype "passive"))
    )
    (net (code "77") (name "unconnected-(DC2--VOUT-Pad4)") (class "Default")
      (node (ref "DC2") (pin "4") (pinfunction "-VOUT_4") (pintype "passive"))
    )
    (net (code "78") (name "unconnected-(IC1-Pad2)") (class "Default")
      (node (ref "IC1") (pin "2") (pinfunction "2_2") (pintype "passive"))
    )
    (net (code "79") (name "unconnected-(IC1-Pad3)") (class "Default")
      (node (ref "IC1") (pin "3") (pinfunction "3_3") (pintype "passive"))
    )
    (net (code "80") (name "unconnected-(IC1-Pad4)") (class "Default")
      (node (ref "IC1") (pin "4") (pinfunction "4_4") (pintype "passive"))
    )
    (net (code "81") (name "unconnected-(IC1-Pad24)") (class "Default")
      (node (ref "IC1") (pin "24") (pinfunction "24_24") (pintype "passive"))
    )
    (net (code "82") (name "unconnected-(IC1-Pad25)") (class "Default")
      (node (ref "IC1") (pin "25") (pinfunction "25_25") (pintype "passive"))
    )
    (net (code "83") (name "unconnected-(IC1-Pad35)") (class "Default")
      (node (ref "IC1") (pin "35") (pinfunction "35_35") (pintype "passive"))
    )
    (net (code "84") (name "unconnected-(IC1-Pad36)") (class "Default")
      (node (ref "IC1") (pin "36") (pinfunction "36_36") (pintype "passive"))
    )
    (net (code "85") (name "unconnected-(IC1-Pad37)") (class "Default")
      (node (ref "IC1") (pin "37") (pinfunction "37_37") (pintype "passive"))
    )
    (net (code "86") (name "unconnected-(IC1-Pad38)") (class "Default")
      (node (ref "IC1") (pin "38") (pinfunction "38_38") (pintype "passive"))
    )
    (net (code "87") (name "unconnected-(IC2-Pad11)") (class "Default")
      (node (ref "IC2") (pin "11") (pinfunction "11_11") (pintype "passive"))
    )
    (net (code "88") (name "unconnected-(IC2-Pad12)") (class "Default")
      (node (ref "IC2") (pin "12") (pinfunction "12_12") (pintype "passive"))
    )
    (net (code "89") (name "unconnected-(IC2-Pad13)") (class "Default")
      (node (ref "IC2") (pin "13") (pinfunction "13_13") (pintype "passive"))
    )
    (net (code "90") (name "unconnected-(IC2-Pad14)") (class "Default")
      (node (ref "IC2") (pin "14") (pinfunction "14_14") (pintype "passive"))
    )
    (net (code "91") (name "unconnected-(OK1-VE-Pad7)") (class "Default")
      (node (ref "OK1") (pin "7") (pinfunction "VE_7") (pintype "passive"))
    )
    (net (code "92") (name "unconnected-(OK2-VE-Pad7)") (class "Default")
      (node (ref "OK2") (pin "7") (pinfunction "VE_7") (pintype "passive"))
    )
    (net (code "93") (name "unconnected-(OK3-VE-Pad7)") (class "Default")
      (node (ref "OK3") (pin "7") (pinfunction "VE_7") (pintype "passive"))
    )
    (net (code "94") (name "unconnected-(OK4-VE-Pad7)") (class "Default")
      (node (ref "OK4") (pin "7") (pinfunction "VE_7") (pintype "passive"))
    )
  )
)
